# Orbiter_PowerSupply_V1.net
KiCad netlist of a schematic drawn in EAGLE
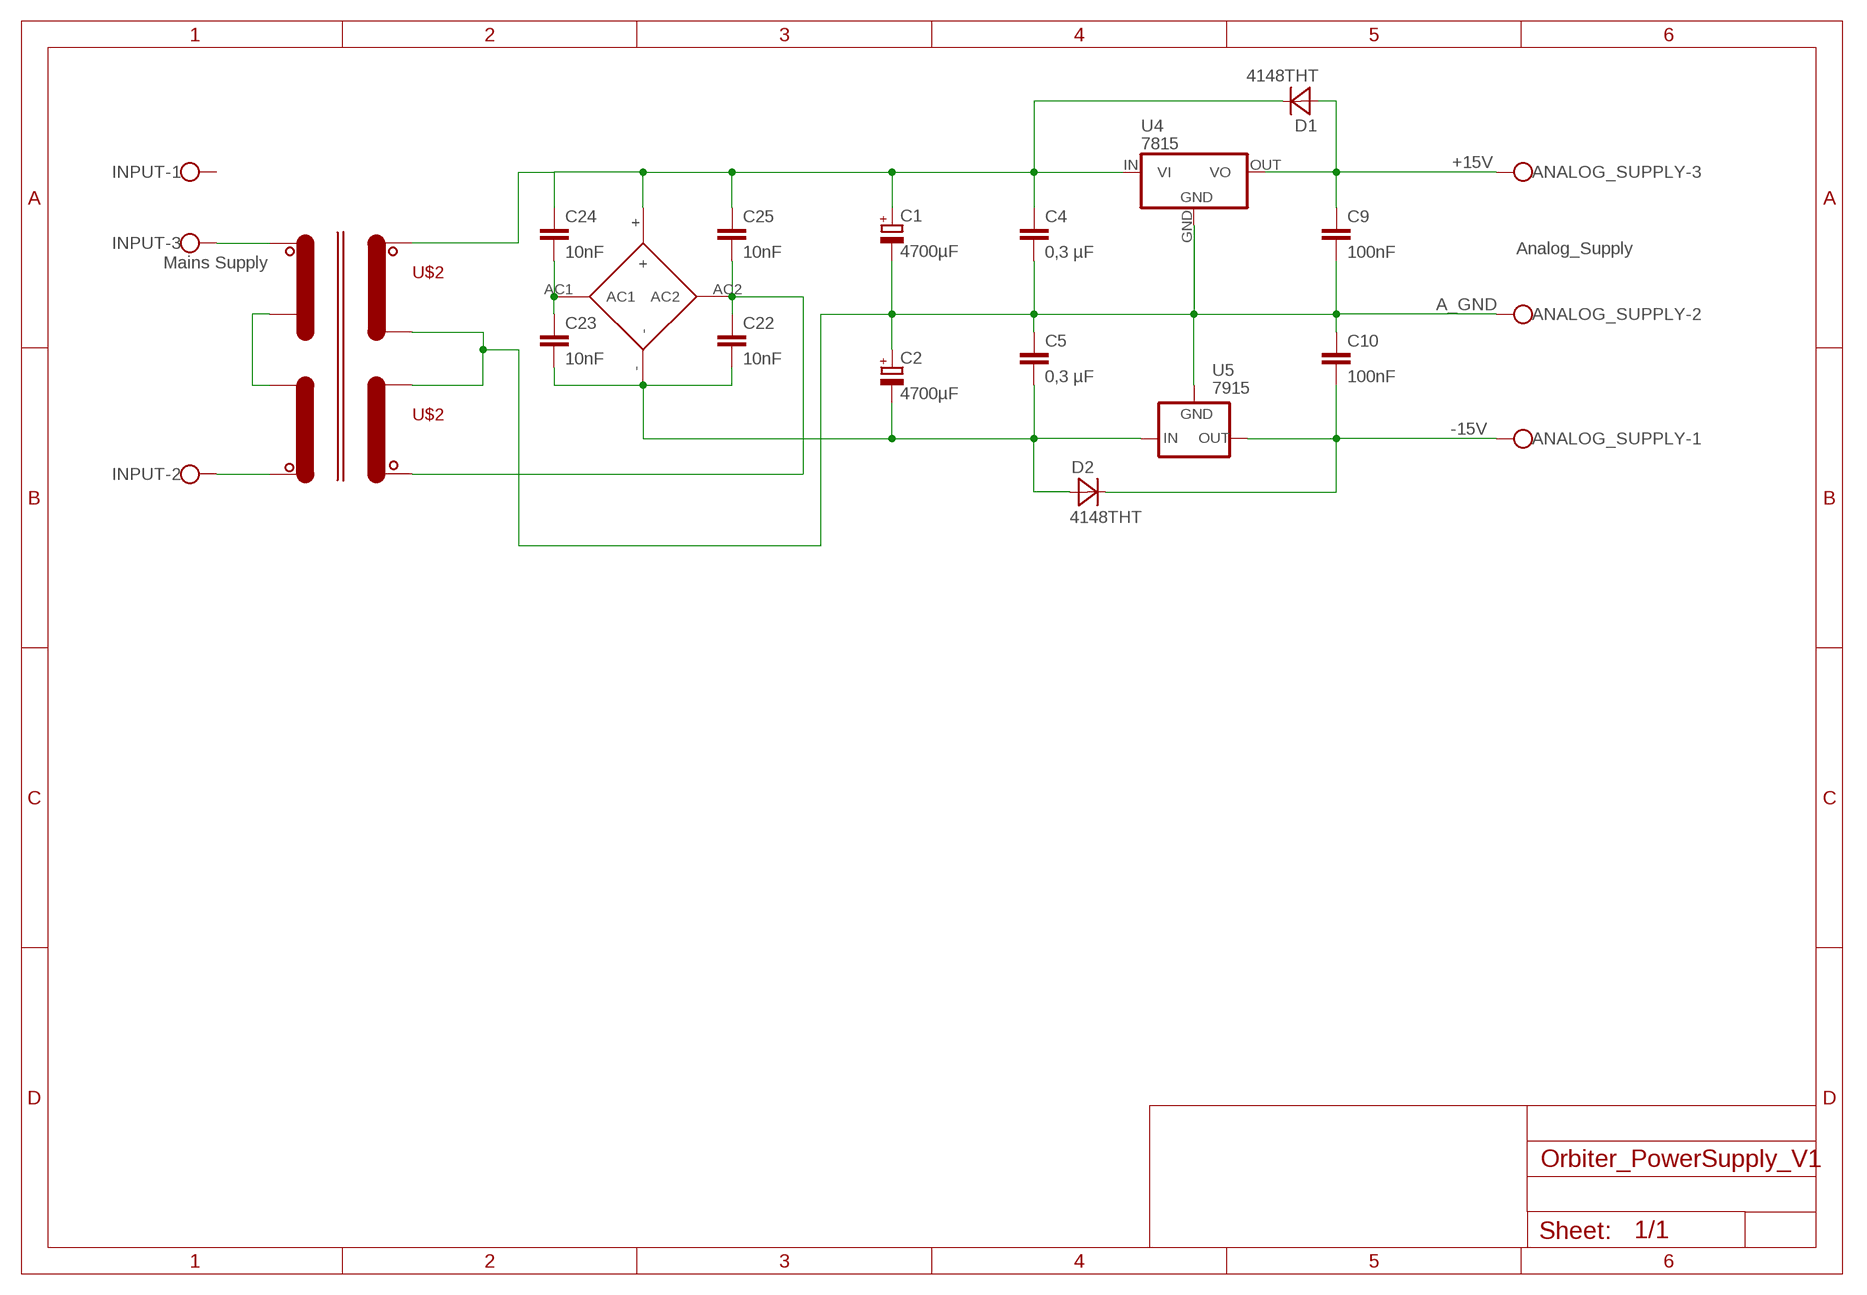
[diagram p0: schematic, sheet 1]

(export (version "E")
  (design (tool "Eeschema 10.0.6"))
  (components
    (comp (ref "ANALOG_SUPPLY")
      (value "Analog_Supply")
      (footprint "eagle-import:W237-103")
      (fields (field (name "MPN") "237-103"))
      (libsource (lib "eagle-import") (part "SCHRAUBKLEMME_3POL"))
    )
    (comp (ref "C1")
      (value "4700µF")
      (footprint "eagle-import:ELECTROLYTIC_16MM")
      (libsource (lib "eagle-import") (part "ELECTROLYTHIC_THT{dblquote}"))
    )
    (comp (ref "C2")
      (value "4700µF")
      (footprint "eagle-import:ELECTROLYTIC_16MM")
      (libsource (lib "eagle-import") (part "ELECTROLYTHIC_THT{dblquote}"))
    )
    (comp (ref "C4")
      (value "0,3 µF")
      (footprint "eagle-import:C5MM")
      (libsource (lib "eagle-import") (part "KONDENSATOR_THT5MM"))
    )
    (comp (ref "C5")
      (value "0,3 µF")
      (footprint "eagle-import:C5MM")
      (libsource (lib "eagle-import") (part "KONDENSATOR_THT5MM"))
    )
    (comp (ref "C9")
      (value "100nF")
      (footprint "eagle-import:C2.5MM")
      (libsource (lib "eagle-import") (part "KONDENSATOR_THT2.5MM"))
    )
    (comp (ref "C10")
      (value "100nF")
      (footprint "eagle-import:C2.5MM")
      (libsource (lib "eagle-import") (part "KONDENSATOR_THT2.5MM"))
    )
    (comp (ref "C22")
      (value "10nF")
      (footprint "eagle-import:C2.5MM")
      (libsource (lib "eagle-import") (part "KONDENSATOR_THT2.5MM"))
    )
    (comp (ref "C23")
      (value "10nF")
      (footprint "eagle-import:C2.5MM")
      (libsource (lib "eagle-import") (part "KONDENSATOR_THT2.5MM"))
    )
    (comp (ref "C24")
      (value "10nF")
      (footprint "eagle-import:C2.5MM")
      (libsource (lib "eagle-import") (part "KONDENSATOR_THT2.5MM"))
    )
    (comp (ref "C25")
      (value "10nF")
      (footprint "eagle-import:C2.5MM")
      (libsource (lib "eagle-import") (part "KONDENSATOR_THT2.5MM"))
    )
    (comp (ref "D1")
      (value "4148THT")
      (footprint "eagle-import:D-5")
      (libsource (lib "eagle-import") (part "4148THT"))
    )
    (comp (ref "D2")
      (value "4148THT")
      (footprint "eagle-import:D-5")
      (libsource (lib "eagle-import") (part "4148THT"))
    )
    (comp (ref "INPUT")
      (value "Mains Supply")
      (footprint "eagle-import:W237-103")
      (fields (field (name "MPN") "237-103"))
      (libsource (lib "eagle-import") (part "SCHRAUBKLEMME_3POL"))
    )
    (comp (ref "U$1")
      (value "GLEICHRICHTER")
      (footprint "eagle-import:SIL_RECTIFER")
      (libsource (lib "eagle-import") (part "GLEICHRICHTER"))
    )
    (comp (ref "U$2")
      (value "PRINTTRAFO_30-600-LPI")
      (footprint "eagle-import:PRINTTRAFO_30-600-LPI")
      (libsource (lib "eagle-import") (part "PRINTTRAFO_30-600-LPI"))
    )
    (comp (ref "U4")
      (value "7815")
      (footprint "eagle-import:78XXS_")
      (libsource (lib "eagle-import") (part "78THT"))
    )
    (comp (ref "U5")
      (value "7915")
      (footprint "eagle-import:79XXS")
      (libsource (lib "eagle-import") (part "79"))
    )
  )
  (nets
    (net (code "1") (name "/+15V") (class "Default")
      (node (ref "ANALOG_SUPPLY") (pin "3") (pinfunction "KL_3") (pintype "passive"))
      (node (ref "C9") (pin "1") (pinfunction "1_1") (pintype "passive"))
      (node (ref "D1") (pin "A") (pinfunction "A_A") (pintype "passive"))
      (node (ref "U4") (pin "OUT") (pinfunction "VO_OUT") (pintype "passive"))
    )
    (net (code "2") (name "/-15V") (class "Default")
      (node (ref "ANALOG_SUPPLY") (pin "1") (pinfunction "KL_1") (pintype "passive"))
      (node (ref "C10") (pin "2") (pinfunction "2_2") (pintype "passive"))
      (node (ref "D2") (pin "C") (pinfunction "C_C") (pintype "passive"))
      (node (ref "U5") (pin "OUT") (pinfunction "OUT_OUT") (pintype "passive"))
    )
    (net (code "3") (name "/A_GND") (class "Default")
      (node (ref "ANALOG_SUPPLY") (pin "2") (pinfunction "KL_2") (pintype "passive"))
      (node (ref "C1") (pin "-") (pinfunction "-_-") (pintype "passive"))
      (node (ref "C10") (pin "1") (pinfunction "1_1") (pintype "passive"))
      (node (ref "C2") (pin "+") (pinfunction "+_+") (pintype "passive"))
      (node (ref "C4") (pin "2") (pinfunction "2_2") (pintype "passive"))
      (node (ref "C5") (pin "1") (pinfunction "1_1") (pintype "passive"))
      (node (ref "C9") (pin "2") (pinfunction "2_2") (pintype "passive"))
      (node (ref "U$2") (pin "6") (pinfunction "6_6") (pintype "bidirectional"))
      (node (ref "U$2") (pin "8") (pinfunction "8_8") (pintype "bidirectional"))
      (node (ref "U4") (pin "GND") (pinfunction "GND_GND") (pintype "passive"))
      (node (ref "U5") (pin "GND") (pinfunction "GND_GND") (pintype "input"))
    )
    (net (code "4") (name "Net-(C2-Pad-)") (class "Default")
      (node (ref "C2") (pin "-") (pinfunction "-_-") (pintype "passive"))
      (node (ref "C22") (pin "2") (pinfunction "2_2") (pintype "passive"))
      (node (ref "C23") (pin "2") (pinfunction "2_2") (pintype "passive"))
      (node (ref "C5") (pin "2") (pinfunction "2_2") (pintype "passive"))
      (node (ref "D2") (pin "A") (pinfunction "A_A") (pintype "passive"))
      (node (ref "U$1") (pin "-") (pinfunction "-_-") (pintype "bidirectional"))
      (node (ref "U5") (pin "IN") (pinfunction "IN_IN") (pintype "input"))
    )
    (net (code "5") (name "Net-(C22-Pad1)") (class "Default")
      (node (ref "C22") (pin "1") (pinfunction "1_1") (pintype "passive"))
      (node (ref "C25") (pin "2") (pinfunction "2_2") (pintype "passive"))
      (node (ref "U$1") (pin "AC2") (pinfunction "AC2_AC2") (pintype "bidirectional"))
      (node (ref "U$2") (pin "5") (pinfunction "5_5") (pintype "bidirectional"))
    )
    (net (code "6") (name "Net-(C23-Pad1)") (class "Default")
      (node (ref "C23") (pin "1") (pinfunction "1_1") (pintype "passive"))
      (node (ref "C24") (pin "2") (pinfunction "2_2") (pintype "passive"))
      (node (ref "U$1") (pin "AC1") (pinfunction "AC1_AC1") (pintype "bidirectional"))
    )
    (net (code "7") (name "Net-(INPUTB-KL)") (class "Default")
      (node (ref "INPUT") (pin "2") (pinfunction "KL_2") (pintype "passive"))
      (node (ref "U$2") (pin "1") (pinfunction "1_1") (pintype "bidirectional"))
    )
    (net (code "8") (name "Net-(INPUTC-KL)") (class "Default")
      (node (ref "INPUT") (pin "3") (pinfunction "KL_3") (pintype "passive"))
      (node (ref "U$2") (pin "3") (pinfunction "3_3") (pintype "bidirectional"))
    )
    (net (code "9") (name "Net-(U$2-Pad2)") (class "Default")
      (node (ref "U$2") (pin "2") (pinfunction "2_2") (pintype "bidirectional"))
      (node (ref "U$2") (pin "4") (pinfunction "4_4") (pintype "bidirectional"))
    )
    (net (code "10") (name "Net-(U4-VI)") (class "Default")
      (node (ref "C1") (pin "+") (pinfunction "+_+") (pintype "passive"))
      (node (ref "C24") (pin "1") (pinfunction "1_1") (pintype "passive"))
      (node (ref "C25") (pin "1") (pinfunction "1_1") (pintype "passive"))
      (node (ref "C4") (pin "1") (pinfunction "1_1") (pintype "passive"))
      (node (ref "D1") (pin "C") (pinfunction "C_C") (pintype "passive"))
      (node (ref "U$1") (pin "+") (pinfunction "+_+") (pintype "bidirectional"))
      (node (ref "U$2") (pin "7") (pinfunction "7_7") (pintype "bidirectional"))
      (node (ref "U4") (pin "IN") (pinfunction "VI_IN") (pintype "input"))
    )
    (net (code "11") (name "unconnected-(INPUTA-KL-Pad1)") (class "Default")
      (node (ref "INPUT") (pin "1") (pinfunction "KL_1") (pintype "passive"))
    )
  )
)
